# cellpilot.net
KiCad netlist of a schematic drawn in EAGLE
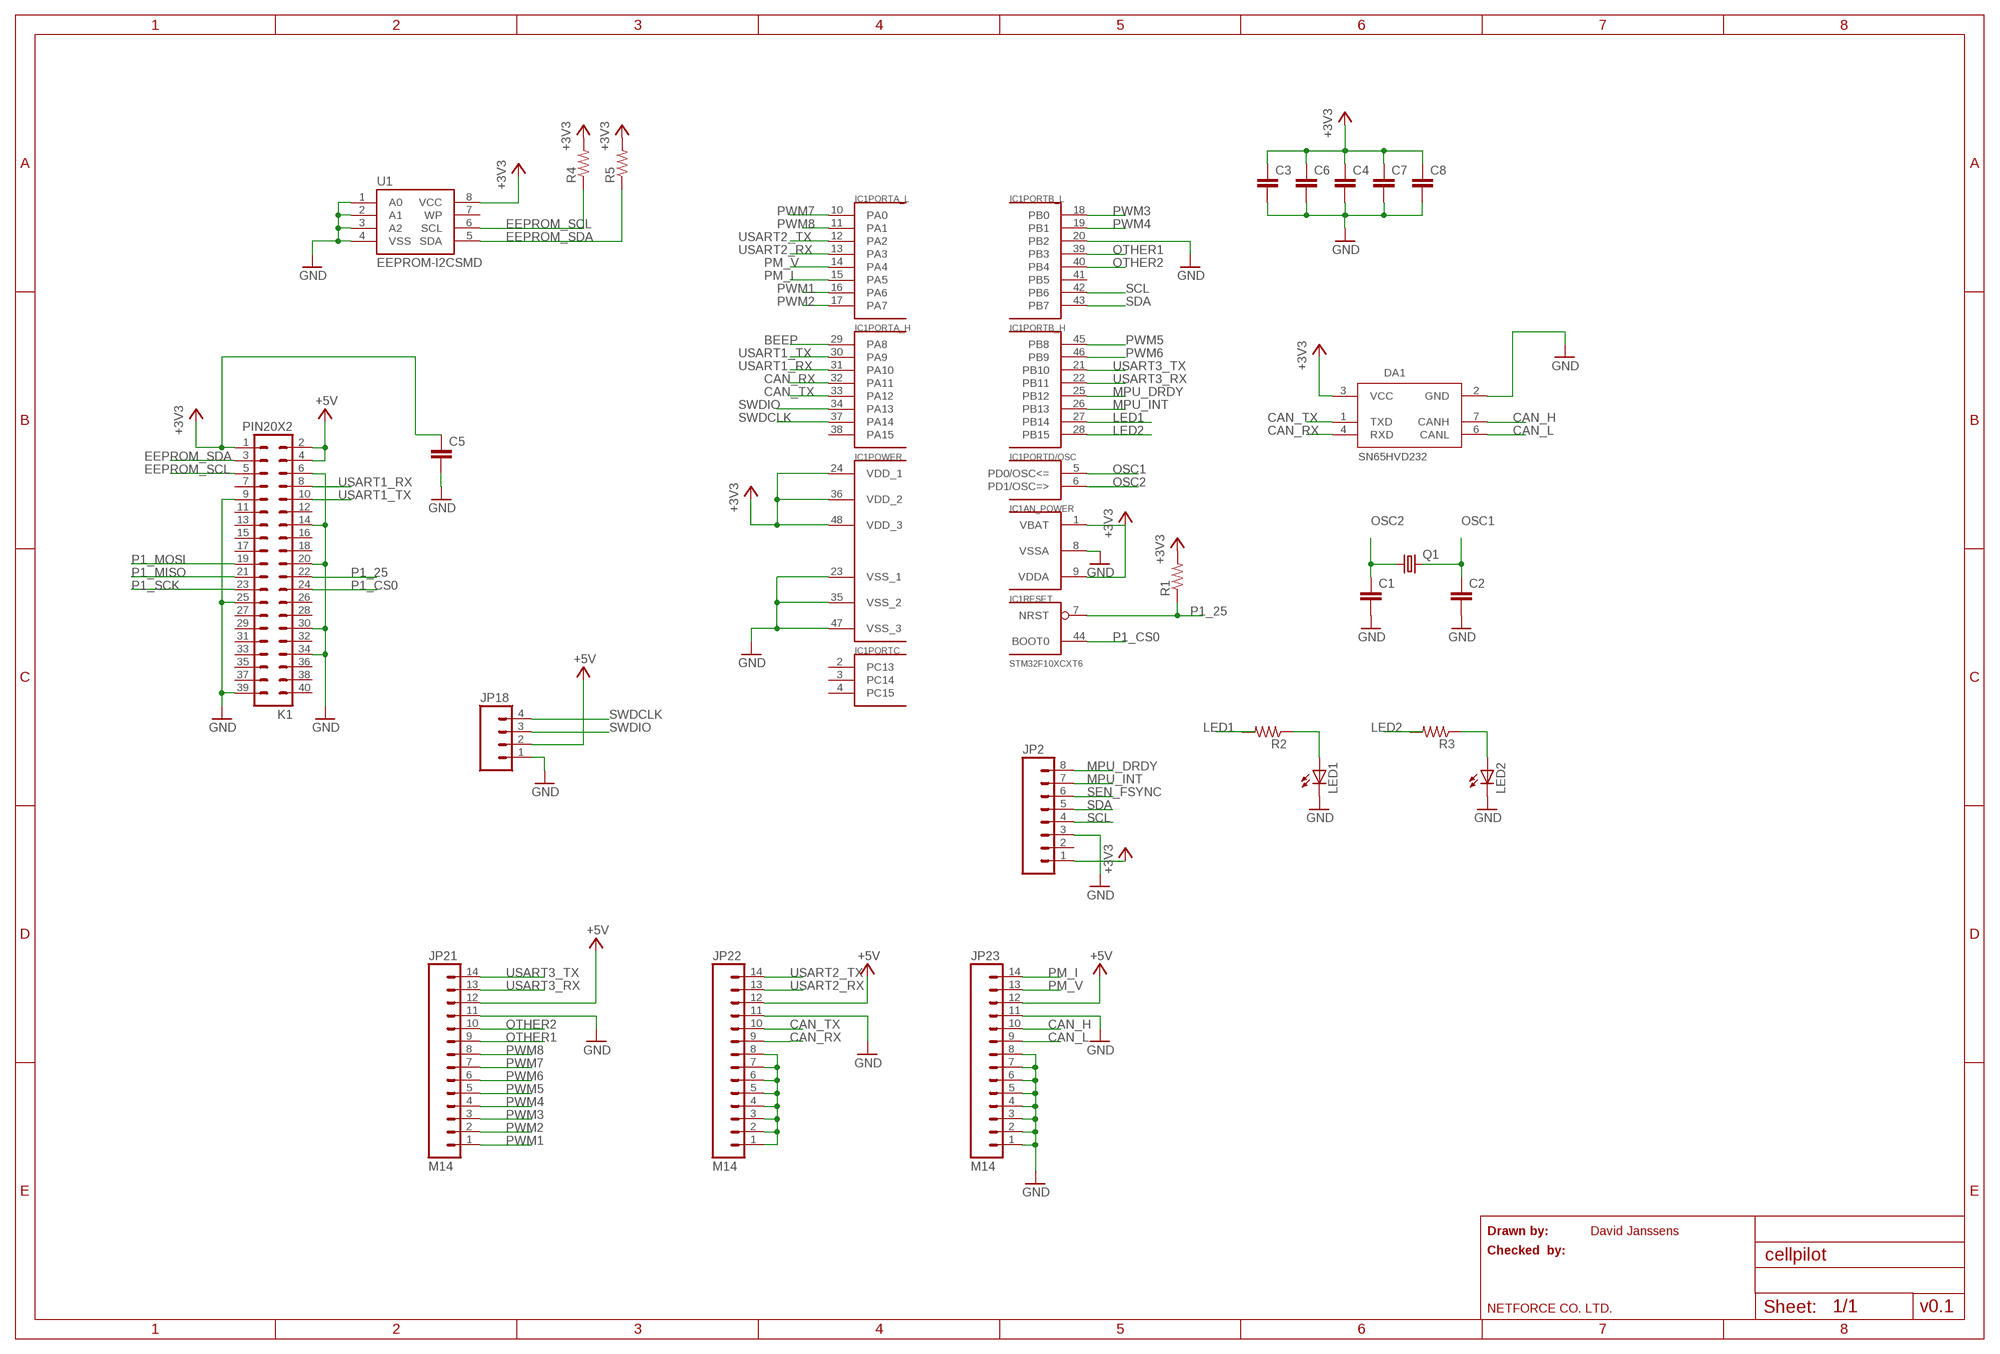
[diagram p0: schematic, sheet 1]

(export (version "E")
  (design (tool "Eeschema 10.0.6"))
  (components
    (comp (ref "C1")
      (value "CAP0805")
      (footprint "eagle-import:0805")
      (libsource (lib "eagle-import") (part "CAP0805"))
    )
    (comp (ref "C2")
      (value "CAP0805")
      (footprint "eagle-import:0805")
      (libsource (lib "eagle-import") (part "CAP0805"))
    )
    (comp (ref "C3")
      (value "CAP0805")
      (footprint "eagle-import:0805")
      (libsource (lib "eagle-import") (part "CAP0805"))
    )
    (comp (ref "C4")
      (value "CAP0805")
      (footprint "eagle-import:0805")
      (libsource (lib "eagle-import") (part "CAP0805"))
    )
    (comp (ref "C5")
      (value "CAP0805")
      (footprint "eagle-import:0805")
      (libsource (lib "eagle-import") (part "CAP0805"))
    )
    (comp (ref "C6")
      (value "CAP0805")
      (footprint "eagle-import:0805")
      (libsource (lib "eagle-import") (part "CAP0805"))
    )
    (comp (ref "C7")
      (value "CAP0805")
      (footprint "eagle-import:0805")
      (libsource (lib "eagle-import") (part "CAP0805"))
    )
    (comp (ref "C8")
      (value "CAP0805")
      (footprint "eagle-import:0805")
      (libsource (lib "eagle-import") (part "CAP0805"))
    )
    (comp (ref "DA1")
      (value "SN65HVD232")
      (footprint "eagle-import:SO08")
      (libsource (lib "eagle-import") (part "SN65HVD232"))
    )
    (comp (ref "IC1")
      (value "STM32F10XCXT6")
      (footprint "eagle-import:TQFP48")
      (libsource (lib "eagle-import") (part "STM32F10XCXT6"))
    )
    (comp (ref "JP2")
      (value "M08")
      (footprint "eagle-import:1X08_ROUND")
      (libsource (lib "eagle-import") (part "M08"))
    )
    (comp (ref "JP18")
      (value "M04PTH")
      (footprint "eagle-import:1X04")
      (libsource (lib "eagle-import") (part "M04PTH"))
    )
    (comp (ref "JP21")
      (value "M14")
      (footprint "eagle-import:1X14")
      (libsource (lib "eagle-import") (part "M14"))
    )
    (comp (ref "JP22")
      (value "M14")
      (footprint "eagle-import:1X14")
      (libsource (lib "eagle-import") (part "M14"))
    )
    (comp (ref "JP23")
      (value "M14")
      (footprint "eagle-import:1X14")
      (libsource (lib "eagle-import") (part "M14"))
    )
    (comp (ref "K1")
      (value "PIN20X2")
      (footprint "eagle-import:PIN_20X2")
      (libsource (lib "eagle-import") (part "PIN20X2"))
    )
    (comp (ref "LED1")
      (value "LED3MM")
      (footprint "eagle-import:LED3MM")
      (libsource (lib "eagle-import") (part "LED3MM"))
    )
    (comp (ref "LED2")
      (value "LED3MM")
      (footprint "eagle-import:LED3MM")
      (libsource (lib "eagle-import") (part "LED3MM"))
    )
    (comp (ref "Q1")
      (value "CRYSTALHC49S")
      (footprint "eagle-import:HC49_S")
      (libsource (lib "eagle-import") (part "CRYSTALHC49S"))
    )
    (comp (ref "R1")
      (value "RESISTOR0805-RES")
      (footprint "eagle-import:0805")
      (libsource (lib "eagle-import") (part "RESISTOR0805-RES"))
    )
    (comp (ref "R2")
      (value "RESISTOR0805-RES")
      (footprint "eagle-import:0805")
      (libsource (lib "eagle-import") (part "RESISTOR0805-RES"))
    )
    (comp (ref "R3")
      (value "RESISTOR0805-RES")
      (footprint "eagle-import:0805")
      (libsource (lib "eagle-import") (part "RESISTOR0805-RES"))
    )
    (comp (ref "R4")
      (value "RESISTOR0805-RES")
      (footprint "eagle-import:0805")
      (libsource (lib "eagle-import") (part "RESISTOR0805-RES"))
    )
    (comp (ref "R5")
      (value "RESISTOR0805-RES")
      (footprint "eagle-import:0805")
      (libsource (lib "eagle-import") (part "RESISTOR0805-RES"))
    )
    (comp (ref "U1")
      (value "EEPROM-I2CSMD")
      (footprint "eagle-import:SO08")
      (libsource (lib "eagle-import") (part "EEPROM-I2CSMD"))
    )
  )
  (nets
    (net (code "1") (name "+3V3") (class "Default")
      (node (ref "C3") (pin "1") (pinfunction "1_1") (pintype "passive"))
      (node (ref "C4") (pin "1") (pinfunction "1_1") (pintype "passive"))
      (node (ref "C5") (pin "1") (pinfunction "1_1") (pintype "passive"))
      (node (ref "C6") (pin "1") (pinfunction "1_1") (pintype "passive"))
      (node (ref "C7") (pin "1") (pinfunction "1_1") (pintype "passive"))
      (node (ref "C8") (pin "1") (pinfunction "1_1") (pintype "passive"))
      (node (ref "DA1") (pin "3") (pinfunction "VCC_3") (pintype "power_in"))
      (node (ref "IC1") (pin "1") (pinfunction "VBAT_1") (pintype "power_in"))
      (node (ref "IC1") (pin "24") (pinfunction "VDD_1_24") (pintype "power_in"))
      (node (ref "IC1") (pin "36") (pinfunction "VDD_2_36") (pintype "power_in"))
      (node (ref "IC1") (pin "48") (pinfunction "VDD_3_48") (pintype "power_in"))
      (node (ref "IC1") (pin "9") (pinfunction "VDDA_9") (pintype "power_in"))
      (node (ref "JP2") (pin "1") (pinfunction "1_1") (pintype "passive"))
      (node (ref "K1") (pin "1") (pinfunction "1_1") (pintype "passive"))
      (node (ref "R1") (pin "2") (pinfunction "2_2") (pintype "passive"))
      (node (ref "R4") (pin "2") (pinfunction "2_2") (pintype "passive"))
      (node (ref "R5") (pin "2") (pinfunction "2_2") (pintype "passive"))
      (node (ref "U1") (pin "8") (pinfunction "VCC_8") (pintype "power_in"))
    )
    (net (code "2") (name "+5V") (class "Default")
      (node (ref "JP18") (pin "2") (pinfunction "2_2") (pintype "passive"))
      (node (ref "JP21") (pin "12") (pinfunction "12_12") (pintype "passive"))
      (node (ref "JP22") (pin "12") (pinfunction "12_12") (pintype "passive"))
      (node (ref "JP23") (pin "12") (pinfunction "12_12") (pintype "passive"))
      (node (ref "K1") (pin "2") (pinfunction "2_2") (pintype "passive"))
      (node (ref "K1") (pin "4") (pinfunction "4_4") (pintype "passive"))
    )
    (net (code "3") (name "/BEEP") (class "Default")
      (node (ref "IC1") (pin "29") (pinfunction "PA8_29") (pintype "bidirectional"))
    )
    (net (code "4") (name "/CAN_H") (class "Default")
      (node (ref "DA1") (pin "7") (pinfunction "CANH_7") (pintype "bidirectional"))
      (node (ref "JP23") (pin "10") (pinfunction "10_10") (pintype "passive"))
    )
    (net (code "5") (name "/CAN_L") (class "Default")
      (node (ref "DA1") (pin "6") (pinfunction "CANL_6") (pintype "bidirectional"))
      (node (ref "JP23") (pin "9") (pinfunction "9_9") (pintype "passive"))
    )
    (net (code "6") (name "/CAN_RX") (class "Default")
      (node (ref "DA1") (pin "4") (pinfunction "RXD_4") (pintype "output"))
      (node (ref "IC1") (pin "32") (pinfunction "PA11_32") (pintype "bidirectional"))
      (node (ref "JP22") (pin "9") (pinfunction "9_9") (pintype "passive"))
    )
    (net (code "7") (name "/CAN_TX") (class "Default")
      (node (ref "DA1") (pin "1") (pinfunction "TXD_1") (pintype "input"))
      (node (ref "IC1") (pin "33") (pinfunction "PA12_33") (pintype "bidirectional"))
      (node (ref "JP22") (pin "10") (pinfunction "10_10") (pintype "passive"))
    )
    (net (code "8") (name "/EEPROM_SCL") (class "Default")
      (node (ref "K1") (pin "5") (pinfunction "5_5") (pintype "passive"))
      (node (ref "R4") (pin "1") (pinfunction "1_1") (pintype "passive"))
      (node (ref "U1") (pin "6") (pinfunction "SCL_6") (pintype "bidirectional"))
    )
    (net (code "9") (name "/EEPROM_SDA") (class "Default")
      (node (ref "K1") (pin "3") (pinfunction "3_3") (pintype "passive"))
      (node (ref "R5") (pin "1") (pinfunction "1_1") (pintype "passive"))
      (node (ref "U1") (pin "5") (pinfunction "SDA_5") (pintype "bidirectional"))
    )
    (net (code "10") (name "/LED1") (class "Default")
      (node (ref "IC1") (pin "27") (pinfunction "PB14_27") (pintype "bidirectional"))
      (node (ref "R2") (pin "2") (pinfunction "2_2") (pintype "passive"))
    )
    (net (code "11") (name "/LED2") (class "Default")
      (node (ref "IC1") (pin "28") (pinfunction "PB15_28") (pintype "bidirectional"))
      (node (ref "R3") (pin "2") (pinfunction "2_2") (pintype "passive"))
    )
    (net (code "12") (name "/MPU_DRDY") (class "Default")
      (node (ref "IC1") (pin "25") (pinfunction "PB12_25") (pintype "bidirectional"))
      (node (ref "JP2") (pin "8") (pinfunction "8_8") (pintype "passive"))
    )
    (net (code "13") (name "/MPU_INT") (class "Default")
      (node (ref "IC1") (pin "26") (pinfunction "PB13_26") (pintype "bidirectional"))
      (node (ref "JP2") (pin "7") (pinfunction "7_7") (pintype "passive"))
    )
    (net (code "14") (name "/OSC1") (class "Default")
      (node (ref "C2") (pin "1") (pinfunction "1_1") (pintype "passive"))
      (node (ref "IC1") (pin "5") (pinfunction "PD0/OSC<=_5") (pintype "bidirectional"))
      (node (ref "Q1") (pin "2") (pinfunction "2_2") (pintype "passive"))
    )
    (net (code "15") (name "/OSC2") (class "Default")
      (node (ref "C1") (pin "1") (pinfunction "1_1") (pintype "passive"))
      (node (ref "IC1") (pin "6") (pinfunction "PD1/OSC=>_6") (pintype "bidirectional"))
      (node (ref "Q1") (pin "1") (pinfunction "1_1") (pintype "passive"))
    )
    (net (code "16") (name "/OTHER1") (class "Default")
      (node (ref "IC1") (pin "39") (pinfunction "PB3_39") (pintype "bidirectional"))
      (node (ref "JP21") (pin "9") (pinfunction "9_9") (pintype "passive"))
    )
    (net (code "17") (name "/OTHER2") (class "Default")
      (node (ref "IC1") (pin "40") (pinfunction "PB4_40") (pintype "bidirectional"))
      (node (ref "JP21") (pin "10") (pinfunction "10_10") (pintype "passive"))
    )
    (net (code "18") (name "/P1_25") (class "Default")
      (node (ref "IC1") (pin "7") (pinfunction "NRST_7") (pintype "input"))
      (node (ref "K1") (pin "22") (pinfunction "22_22") (pintype "passive"))
      (node (ref "R1") (pin "1") (pinfunction "1_1") (pintype "passive"))
    )
    (net (code "19") (name "/P1_CS0") (class "Default")
      (node (ref "IC1") (pin "44") (pinfunction "BOOT0_44") (pintype "input"))
      (node (ref "K1") (pin "24") (pinfunction "24_24") (pintype "passive"))
    )
    (net (code "20") (name "/P1_MISO") (class "Default")
      (node (ref "K1") (pin "21") (pinfunction "21_21") (pintype "passive"))
    )
    (net (code "21") (name "/P1_MOSI") (class "Default")
      (node (ref "K1") (pin "19") (pinfunction "19_19") (pintype "passive"))
    )
    (net (code "22") (name "/P1_SCK") (class "Default")
      (node (ref "K1") (pin "23") (pinfunction "23_23") (pintype "passive"))
    )
    (net (code "23") (name "/PM_I") (class "Default")
      (node (ref "IC1") (pin "15") (pinfunction "PA5_15") (pintype "bidirectional"))
      (node (ref "JP23") (pin "14") (pinfunction "14_14") (pintype "passive"))
    )
    (net (code "24") (name "/PM_V") (class "Default")
      (node (ref "IC1") (pin "14") (pinfunction "PA4_14") (pintype "bidirectional"))
      (node (ref "JP23") (pin "13") (pinfunction "13_13") (pintype "passive"))
    )
    (net (code "25") (name "/PWM1") (class "Default")
      (node (ref "IC1") (pin "16") (pinfunction "PA6_16") (pintype "bidirectional"))
      (node (ref "JP21") (pin "1") (pinfunction "1_1") (pintype "passive"))
    )
    (net (code "26") (name "/PWM2") (class "Default")
      (node (ref "IC1") (pin "17") (pinfunction "PA7_17") (pintype "bidirectional"))
      (node (ref "JP21") (pin "2") (pinfunction "2_2") (pintype "passive"))
    )
    (net (code "27") (name "/PWM3") (class "Default")
      (node (ref "IC1") (pin "18") (pinfunction "PB0_18") (pintype "bidirectional"))
      (node (ref "JP21") (pin "3") (pinfunction "3_3") (pintype "passive"))
    )
    (net (code "28") (name "/PWM4") (class "Default")
      (node (ref "IC1") (pin "19") (pinfunction "PB1_19") (pintype "bidirectional"))
      (node (ref "JP21") (pin "4") (pinfunction "4_4") (pintype "passive"))
    )
    (net (code "29") (name "/PWM5") (class "Default")
      (node (ref "IC1") (pin "45") (pinfunction "PB8_45") (pintype "bidirectional"))
      (node (ref "JP21") (pin "5") (pinfunction "5_5") (pintype "passive"))
    )
    (net (code "30") (name "/PWM6") (class "Default")
      (node (ref "IC1") (pin "46") (pinfunction "PB9_46") (pintype "bidirectional"))
      (node (ref "JP21") (pin "6") (pinfunction "6_6") (pintype "passive"))
    )
    (net (code "31") (name "/PWM7") (class "Default")
      (node (ref "IC1") (pin "10") (pinfunction "PA0_10") (pintype "bidirectional"))
      (node (ref "JP21") (pin "7") (pinfunction "7_7") (pintype "passive"))
    )
    (net (code "32") (name "/PWM8") (class "Default")
      (node (ref "IC1") (pin "11") (pinfunction "PA1_11") (pintype "bidirectional"))
      (node (ref "JP21") (pin "8") (pinfunction "8_8") (pintype "passive"))
    )
    (net (code "33") (name "/SCL") (class "Default")
      (node (ref "IC1") (pin "42") (pinfunction "PB6_42") (pintype "bidirectional"))
      (node (ref "JP2") (pin "4") (pinfunction "4_4") (pintype "passive"))
    )
    (net (code "34") (name "/SDA") (class "Default")
      (node (ref "IC1") (pin "43") (pinfunction "PB7_43") (pintype "bidirectional"))
      (node (ref "JP2") (pin "5") (pinfunction "5_5") (pintype "passive"))
    )
    (net (code "35") (name "/SEN_FSYNC") (class "Default")
      (node (ref "JP2") (pin "6") (pinfunction "6_6") (pintype "passive"))
    )
    (net (code "36") (name "/SWDCLK") (class "Default")
      (node (ref "IC1") (pin "37") (pinfunction "PA14_37") (pintype "bidirectional"))
      (node (ref "JP18") (pin "4") (pinfunction "4_4") (pintype "passive"))
    )
    (net (code "37") (name "/SWDIO") (class "Default")
      (node (ref "IC1") (pin "34") (pinfunction "PA13_34") (pintype "bidirectional"))
      (node (ref "JP18") (pin "3") (pinfunction "3_3") (pintype "passive"))
    )
    (net (code "38") (name "/USART1_RX") (class "Default")
      (node (ref "IC1") (pin "31") (pinfunction "PA10_31") (pintype "bidirectional"))
      (node (ref "K1") (pin "8") (pinfunction "8_8") (pintype "passive"))
    )
    (net (code "39") (name "/USART1_TX") (class "Default")
      (node (ref "IC1") (pin "30") (pinfunction "PA9_30") (pintype "bidirectional"))
      (node (ref "K1") (pin "10") (pinfunction "10_10") (pintype "passive"))
    )
    (net (code "40") (name "/USART2_RX") (class "Default")
      (node (ref "IC1") (pin "13") (pinfunction "PA3_13") (pintype "bidirectional"))
      (node (ref "JP22") (pin "13") (pinfunction "13_13") (pintype "passive"))
    )
    (net (code "41") (name "/USART2_TX") (class "Default")
      (node (ref "IC1") (pin "12") (pinfunction "PA2_12") (pintype "bidirectional"))
      (node (ref "JP22") (pin "14") (pinfunction "14_14") (pintype "passive"))
    )
    (net (code "42") (name "/USART3_RX") (class "Default")
      (node (ref "IC1") (pin "22") (pinfunction "PB11_22") (pintype "bidirectional"))
      (node (ref "JP21") (pin "13") (pinfunction "13_13") (pintype "passive"))
    )
    (net (code "43") (name "/USART3_TX") (class "Default")
      (node (ref "IC1") (pin "21") (pinfunction "PB10_21") (pintype "bidirectional"))
      (node (ref "JP21") (pin "14") (pinfunction "14_14") (pintype "passive"))
    )
    (net (code "44") (name "GND") (class "Default")
      (node (ref "C1") (pin "2") (pinfunction "2_2") (pintype "passive"))
      (node (ref "C2") (pin "2") (pinfunction "2_2") (pintype "passive"))
      (node (ref "C3") (pin "2") (pinfunction "2_2") (pintype "passive"))
      (node (ref "C4") (pin "2") (pinfunction "2_2") (pintype "passive"))
      (node (ref "C5") (pin "2") (pinfunction "2_2") (pintype "passive"))
      (node (ref "C6") (pin "2") (pinfunction "2_2") (pintype "passive"))
      (node (ref "C7") (pin "2") (pinfunction "2_2") (pintype "passive"))
      (node (ref "C8") (pin "2") (pinfunction "2_2") (pintype "passive"))
      (node (ref "DA1") (pin "2") (pinfunction "GND_2") (pintype "power_in"))
      (node (ref "IC1") (pin "20") (pinfunction "PB2_20") (pintype "bidirectional"))
      (node (ref "IC1") (pin "23") (pinfunction "VSS_1_23") (pintype "power_in"))
      (node (ref "IC1") (pin "35") (pinfunction "VSS_2_35") (pintype "power_in"))
      (node (ref "IC1") (pin "47") (pinfunction "VSS_3_47") (pintype "power_in"))
      (node (ref "IC1") (pin "8") (pinfunction "VSSA_8") (pintype "power_in"))
      (node (ref "JP18") (pin "1") (pinfunction "1_1") (pintype "passive"))
      (node (ref "JP2") (pin "3") (pinfunction "3_3") (pintype "passive"))
      (node (ref "JP21") (pin "11") (pinfunction "11_11") (pintype "passive"))
      (node (ref "JP22") (pin "11") (pinfunction "11_11") (pintype "passive"))
      (node (ref "JP23") (pin "1") (pinfunction "1_1") (pintype "passive"))
      (node (ref "JP23") (pin "11") (pinfunction "11_11") (pintype "passive"))
      (node (ref "JP23") (pin "2") (pinfunction "2_2") (pintype "passive"))
      (node (ref "JP23") (pin "3") (pinfunction "3_3") (pintype "passive"))
      (node (ref "JP23") (pin "4") (pinfunction "4_4") (pintype "passive"))
      (node (ref "JP23") (pin "5") (pinfunction "5_5") (pintype "passive"))
      (node (ref "JP23") (pin "6") (pinfunction "6_6") (pintype "passive"))
      (node (ref "JP23") (pin "7") (pinfunction "7_7") (pintype "passive"))
      (node (ref "JP23") (pin "8") (pinfunction "8_8") (pintype "passive"))
      (node (ref "K1") (pin "14") (pinfunction "14_14") (pintype "passive"))
      (node (ref "K1") (pin "20") (pinfunction "20_20") (pintype "passive"))
      (node (ref "K1") (pin "25") (pinfunction "25_25") (pintype "passive"))
      (node (ref "K1") (pin "30") (pinfunction "30_30") (pintype "passive"))
      (node (ref "K1") (pin "34") (pinfunction "34_34") (pintype "passive"))
      (node (ref "K1") (pin "39") (pinfunction "39_39") (pintype "passive"))
      (node (ref "K1") (pin "6") (pinfunction "6_6") (pintype "passive"))
      (node (ref "K1") (pin "9") (pinfunction "9_9") (pintype "passive"))
      (node (ref "LED1") (pin "K") (pinfunction "C_K") (pintype "passive"))
      (node (ref "LED2") (pin "K") (pinfunction "C_K") (pintype "passive"))
      (node (ref "U1") (pin "1") (pinfunction "A0_1") (pintype "bidirectional"))
      (node (ref "U1") (pin "2") (pinfunction "A1_2") (pintype "bidirectional"))
      (node (ref "U1") (pin "3") (pinfunction "A2_3") (pintype "bidirectional"))
      (node (ref "U1") (pin "4") (pinfunction "VSS_4") (pintype "power_in"))
    )
    (net (code "45") (name "Net-(JP22-Pad1)") (class "Default")
      (node (ref "JP22") (pin "1") (pinfunction "1_1") (pintype "passive"))
      (node (ref "JP22") (pin "2") (pinfunction "2_2") (pintype "passive"))
      (node (ref "JP22") (pin "3") (pinfunction "3_3") (pintype "passive"))
      (node (ref "JP22") (pin "4") (pinfunction "4_4") (pintype "passive"))
      (node (ref "JP22") (pin "5") (pinfunction "5_5") (pintype "passive"))
      (node (ref "JP22") (pin "6") (pinfunction "6_6") (pintype "passive"))
      (node (ref "JP22") (pin "7") (pinfunction "7_7") (pintype "passive"))
      (node (ref "JP22") (pin "8") (pinfunction "8_8") (pintype "passive"))
    )
    (net (code "46") (name "Net-(LED1-PadA)") (class "Default")
      (node (ref "LED1") (pin "A") (pinfunction "A_A") (pintype "passive"))
      (node (ref "R2") (pin "1") (pinfunction "1_1") (pintype "passive"))
    )
    (net (code "47") (name "Net-(LED2-PadA)") (class "Default")
      (node (ref "LED2") (pin "A") (pinfunction "A_A") (pintype "passive"))
      (node (ref "R3") (pin "1") (pinfunction "1_1") (pintype "passive"))
    )
    (net (code "48") (name "unconnected-(IC1B-PA15-Pad38)") (class "Default")
      (node (ref "IC1") (pin "38") (pinfunction "PA15_38") (pintype "bidirectional"))
    )
    (net (code "49") (name "unconnected-(IC1E-PB5-Pad41)") (class "Default")
      (node (ref "IC1") (pin "41") (pinfunction "PB5_41") (pintype "bidirectional"))
    )
    (net (code "50") (name "unconnected-(IC1F-PC13-Pad2)") (class "Default")
      (node (ref "IC1") (pin "2") (pinfunction "PC13_2") (pintype "bidirectional"))
    )
    (net (code "51") (name "unconnected-(IC1F-PC14-Pad3)") (class "Default")
      (node (ref "IC1") (pin "3") (pinfunction "PC14_3") (pintype "bidirectional"))
    )
    (net (code "52") (name "unconnected-(IC1F-PC15-Pad4)") (class "Default")
      (node (ref "IC1") (pin "4") (pinfunction "PC15_4") (pintype "bidirectional"))
    )
    (net (code "53") (name "unconnected-(JP2-Pad2)") (class "Default")
      (node (ref "JP2") (pin "2") (pinfunction "2_2") (pintype "passive"))
    )
    (net (code "54") (name "unconnected-(K1-Pad7)") (class "Default")
      (node (ref "K1") (pin "7") (pinfunction "7_7") (pintype "passive"))
    )
    (net (code "55") (name "unconnected-(K1-Pad11)") (class "Default")
      (node (ref "K1") (pin "11") (pinfunction "11_11") (pintype "passive"))
    )
    (net (code "56") (name "unconnected-(K1-Pad12)") (class "Default")
      (node (ref "K1") (pin "12") (pinfunction "12_12") (pintype "passive"))
    )
    (net (code "57") (name "unconnected-(K1-Pad13)") (class "Default")
      (node (ref "K1") (pin "13") (pinfunction "13_13") (pintype "passive"))
    )
    (net (code "58") (name "unconnected-(K1-Pad15)") (class "Default")
      (node (ref "K1") (pin "15") (pinfunction "15_15") (pintype "passive"))
    )
    (net (code "59") (name "unconnected-(K1-Pad16)") (class "Default")
      (node (ref "K1") (pin "16") (pinfunction "16_16") (pintype "passive"))
    )
    (net (code "60") (name "unconnected-(K1-Pad17)") (class "Default")
      (node (ref "K1") (pin "17") (pinfunction "17_17") (pintype "passive"))
    )
    (net (code "61") (name "unconnected-(K1-Pad18)") (class "Default")
      (node (ref "K1") (pin "18") (pinfunction "18_18") (pintype "passive"))
    )
    (net (code "62") (name "unconnected-(K1-Pad26)") (class "Default")
      (node (ref "K1") (pin "26") (pinfunction "26_26") (pintype "passive"))
    )
    (net (code "63") (name "unconnected-(K1-Pad27)") (class "Default")
      (node (ref "K1") (pin "27") (pinfunction "27_27") (pintype "passive"))
    )
    (net (code "64") (name "unconnected-(K1-Pad28)") (class "Default")
      (node (ref "K1") (pin "28") (pinfunction "28_28") (pintype "passive"))
    )
    (net (code "65") (name "unconnected-(K1-Pad29)") (class "Default")
      (node (ref "K1") (pin "29") (pinfunction "29_29") (pintype "passive"))
    )
    (net (code "66") (name "unconnected-(K1-Pad31)") (class "Default")
      (node (ref "K1") (pin "31") (pinfunction "31_31") (pintype "passive"))
    )
    (net (code "67") (name "unconnected-(K1-Pad32)") (class "Default")
      (node (ref "K1") (pin "32") (pinfunction "32_32") (pintype "passive"))
    )
    (net (code "68") (name "unconnected-(K1-Pad33)") (class "Default")
      (node (ref "K1") (pin "33") (pinfunction "33_33") (pintype "passive"))
    )
    (net (code "69") (name "unconnected-(K1-Pad35)") (class "Default")
      (node (ref "K1") (pin "35") (pinfunction "35_35") (pintype "passive"))
    )
    (net (code "70") (name "unconnected-(K1-Pad36)") (class "Default")
      (node (ref "K1") (pin "36") (pinfunction "36_36") (pintype "passive"))
    )
    (net (code "71") (name "unconnected-(K1-Pad37)") (class "Default")
      (node (ref "K1") (pin "37") (pinfunction "37_37") (pintype "passive"))
    )
    (net (code "72") (name "unconnected-(K1-Pad38)") (class "Default")
      (node (ref "K1") (pin "38") (pinfunction "38_38") (pintype "passive"))
    )
    (net (code "73") (name "unconnected-(K1-Pad40)") (class "Default")
      (node (ref "K1") (pin "40") (pinfunction "40_40") (pintype "passive"))
    )
    (net (code "74") (name "unconnected-(U1-WP-Pad7)") (class "Default")
      (node (ref "U1") (pin "7") (pinfunction "WP_7") (pintype "bidirectional"))
    )
  )
)
